# 03_Mechanicals.net
KiCad netlist of a schematic drawn in Altium Designer
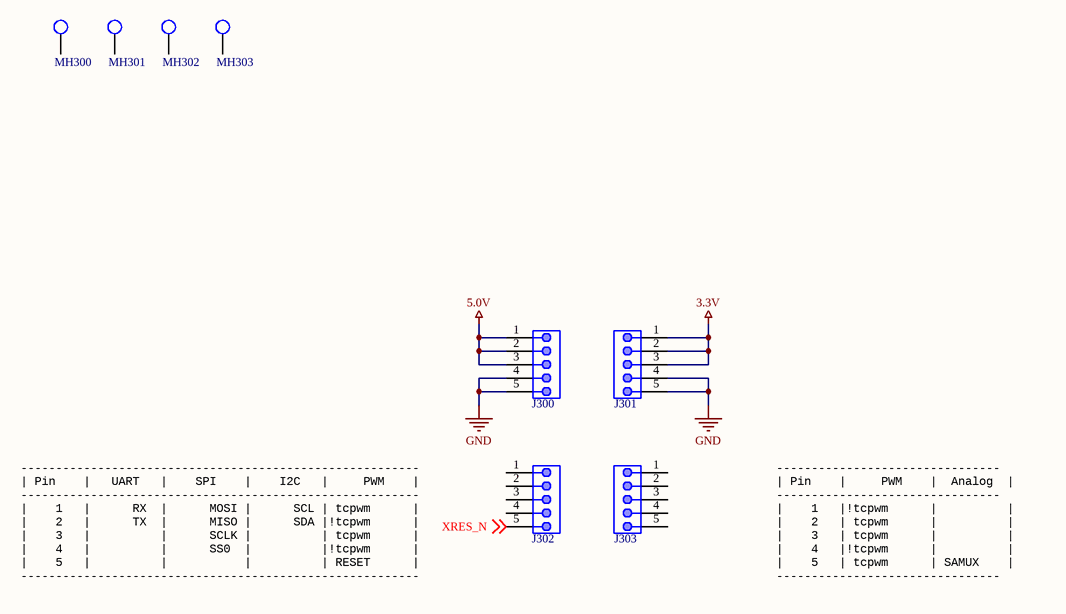
[diagram p0: 03_Mechanicals.SchDoc]

(export (version "E")
  (design (tool "Eeschema 10.0.6"))
  (components
    (comp (ref "J300")
      (value "CONN_HEADER_MALE_1x5")
      (footprint "HDR1X5")
      (description "Header, 5-Pin")
      (libsource (lib "") (part "CONN_HEADER_MALE_1x5_1"))
    )
    (comp (ref "J301")
      (value "CONN_HEADER_MALE_1x5")
      (footprint "HDR1X5")
      (description "Header, 5-Pin")
      (libsource (lib "Connectors") (part "CONN_HEADER_MALE_1x5"))
    )
    (comp (ref "J302")
      (value "CONN_HEADER_MALE_1x5")
      (footprint "HDR1X5")
      (description "Header, 5-Pin")
      (libsource (lib "") (part "CONN_HEADER_MALE_1x5_1"))
    )
    (comp (ref "J303")
      (value "CONN_HEADER_MALE_1x5")
      (footprint "HDR1X5")
      (description "Header, 5-Pin")
      (libsource (lib "Connectors") (part "CONN_HEADER_MALE_1x5"))
    )
    (comp (ref "MH300")
      (value "MHOLE_2_55MM")
      (footprint "MHOLE_2_55MM")
      (description "Mounting Holde")
      (fields (field (name "MANUFACTURER PART NUMBER") "UW MTHOLE"))
      (libsource (lib "ece315-2018-fall") (part "MHOLE_2_55MM"))
    )
    (comp (ref "MH301")
      (value "MHOLE_2_55MM")
      (footprint "MHOLE_2_55MM")
      (description "Mounting Holde")
      (fields (field (name "MANUFACTURER PART NUMBER") "UW MTHOLE"))
      (libsource (lib "ece315-2018-fall") (part "MHOLE_2_55MM"))
    )
    (comp (ref "MH302")
      (value "MHOLE_2_55MM")
      (footprint "MHOLE_2_55MM")
      (description "Mounting Holde")
      (fields (field (name "MANUFACTURER PART NUMBER") "UW MTHOLE"))
      (libsource (lib "ece315-2018-fall") (part "MHOLE_2_55MM"))
    )
    (comp (ref "MH303")
      (value "MHOLE_2_55MM")
      (footprint "MHOLE_2_55MM")
      (description "Mounting Holde")
      (fields (field (name "MANUFACTURER PART NUMBER") "UW MTHOLE"))
      (libsource (lib "ece315-2018-fall") (part "MHOLE_2_55MM"))
    )
  )
  (nets
    (net (code "1") (name "3.3V") (class "Default")
      (node (ref "J301") (pin "1") (pinfunction "1_1") (pintype "passive"))
      (node (ref "J301") (pin "2") (pinfunction "2_2") (pintype "passive"))
      (node (ref "J301") (pin "3") (pinfunction "3_3") (pintype "passive"))
    )
    (net (code "2") (name "5.0V") (class "Default")
      (node (ref "J300") (pin "1") (pinfunction "1_1") (pintype "passive"))
      (node (ref "J300") (pin "2") (pinfunction "2_2") (pintype "passive"))
      (node (ref "J300") (pin "3") (pinfunction "3_3") (pintype "passive"))
    )
    (net (code "3") (name "GND") (class "Default")
      (node (ref "J300") (pin "4") (pinfunction "4_4") (pintype "passive"))
      (node (ref "J300") (pin "5") (pinfunction "5_5") (pintype "passive"))
      (node (ref "J301") (pin "4") (pinfunction "4_4") (pintype "passive"))
      (node (ref "J301") (pin "5") (pinfunction "5_5") (pintype "passive"))
    )
    (net (code "4") (name "XRES_N") (class "Default")
      (node (ref "J302") (pin "5") (pinfunction "5_5") (pintype "passive"))
    )
    (net (code "5") (name "unconnected-(J302-Pad1)") (class "Default")
      (node (ref "J302") (pin "1") (pinfunction "1_1") (pintype "passive"))
    )
    (net (code "6") (name "unconnected-(J302-Pad2)") (class "Default")
      (node (ref "J302") (pin "2") (pinfunction "2_2") (pintype "passive"))
    )
    (net (code "7") (name "unconnected-(J302-Pad3)") (class "Default")
      (node (ref "J302") (pin "3") (pinfunction "3_3") (pintype "passive"))
    )
    (net (code "8") (name "unconnected-(J302-Pad4)") (class "Default")
      (node (ref "J302") (pin "4") (pinfunction "4_4") (pintype "passive"))
    )
    (net (code "9") (name "unconnected-(J303-Pad1)") (class "Default")
      (node (ref "J303") (pin "1") (pinfunction "1_1") (pintype "passive"))
    )
    (net (code "10") (name "unconnected-(J303-Pad2)") (class "Default")
      (node (ref "J303") (pin "2") (pinfunction "2_2") (pintype "passive"))
    )
    (net (code "11") (name "unconnected-(J303-Pad3)") (class "Default")
      (node (ref "J303") (pin "3") (pinfunction "3_3") (pintype "passive"))
    )
    (net (code "12") (name "unconnected-(J303-Pad4)") (class "Default")
      (node (ref "J303") (pin "4") (pinfunction "4_4") (pintype "passive"))
    )
    (net (code "13") (name "unconnected-(J303-Pad5)") (class "Default")
      (node (ref "J303") (pin "5") (pinfunction "5_5") (pintype "passive"))
    )
    (net (code "14") (name "unconnected-(MH300-Pad1)") (class "Default")
      (node (ref "MH300") (pin "1") (pintype "passive"))
    )
    (net (code "15") (name "unconnected-(MH301-Pad1)") (class "Default")
      (node (ref "MH301") (pin "1") (pintype "passive"))
    )
    (net (code "16") (name "unconnected-(MH302-Pad1)") (class "Default")
      (node (ref "MH302") (pin "1") (pintype "passive"))
    )
    (net (code "17") (name "unconnected-(MH303-Pad1)") (class "Default")
      (node (ref "MH303") (pin "1") (pintype "passive"))
    )
  )
)
